# Amplifier.net
KiCad netlist of a schematic drawn in Altium Designer
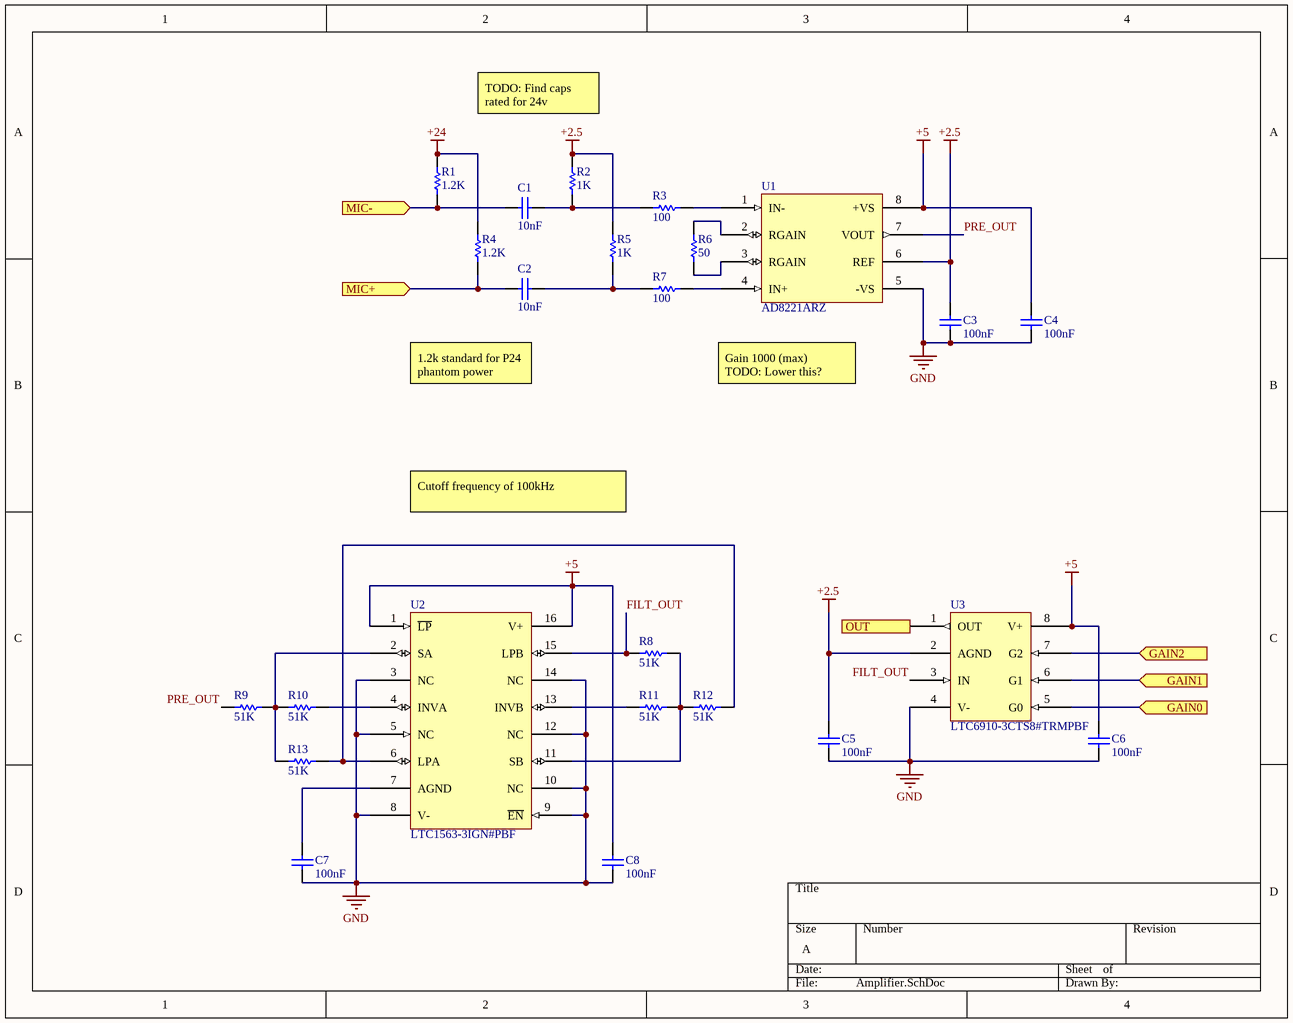
[diagram p0: Amplifier.SchDoc]

(export (version "E")
  (design (tool "Eeschema 10.0.6"))
  (components
    (comp (ref "C1")
      (value "10nF")
      (footprint "CAPC1608X10M")
      (description "GRM188 0603(1.6mm*0.8mm) ±5% and ±10% (15pF-2.2uF) SMD Capacitor")
      (fields (field (name "PUBLISHER") "Altium Limited"))
      (libsource (lib "Acoustics") (part "GRM188"))
    )
    (comp (ref "C2")
      (value "10nF")
      (footprint "CAPC1608X10M")
      (description "GRM188 0603(1.6mm*0.8mm) ±5% and ±10% (15pF-2.2uF) SMD Capacitor")
      (fields (field (name "PUBLISHER") "Altium Limited"))
      (libsource (lib "Acoustics") (part "GRM188"))
    )
    (comp (ref "C3")
      (value "100nF")
      (footprint "CAPC1608X10M")
      (description "GRM188 0603(1.6mm*0.8mm) ±5% and ±10% (15pF-2.2uF) SMD Capacitor")
      (fields (field (name "PUBLISHER") "Altium Limited"))
      (libsource (lib "Acoustics") (part "GRM188"))
    )
    (comp (ref "C4")
      (value "100nF")
      (footprint "CAPC1608X10M")
      (description "GRM188 0603(1.6mm*0.8mm) ±5% and ±10% (15pF-2.2uF) SMD Capacitor")
      (fields (field (name "PUBLISHER") "Altium Limited"))
      (libsource (lib "Acoustics") (part "GRM188"))
    )
    (comp (ref "C5")
      (value "100nF")
      (footprint "CAPC1608X10M")
      (description "GRM188 0603(1.6mm*0.8mm) ±5% and ±10% (15pF-2.2uF) SMD Capacitor")
      (fields (field (name "PUBLISHER") "Altium Limited"))
      (libsource (lib "Acoustics") (part "GRM188"))
    )
    (comp (ref "C6")
      (value "100nF")
      (footprint "CAPC1608X10M")
      (description "GRM188 0603(1.6mm*0.8mm) ±5% and ±10% (15pF-2.2uF) SMD Capacitor")
      (fields (field (name "PUBLISHER") "Altium Limited"))
      (libsource (lib "Acoustics") (part "GRM188"))
    )
    (comp (ref "C7")
      (value "100nF")
      (footprint "CAPC1608X10M")
      (description "GRM188 0603(1.6mm*0.8mm) ±5% and ±10% (15pF-2.2uF) SMD Capacitor")
      (fields (field (name "PUBLISHER") "Altium Limited"))
      (libsource (lib "Acoustics") (part "GRM188"))
    )
    (comp (ref "C8")
      (value "100nF")
      (footprint "CAPC1608X10M")
      (description "GRM188 0603(1.6mm*0.8mm) ±5% and ±10% (15pF-2.2uF) SMD Capacitor")
      (fields (field (name "PUBLISHER") "Altium Limited"))
      (libsource (lib "Acoustics") (part "GRM188"))
    )
    (comp (ref "R1")
      (value "1.2K")
      (footprint "RESC1608X06M")
      (description "RC0603 JR-07 0603 (1.6mm*0.8mm) ±1% 1% (0R-4.7MR) chip resistor")
      (fields (field (name "PUBLISHER") "Altium Limited"))
      (libsource (lib "Acoustics") (part "RC0603_JR07"))
    )
    (comp (ref "R2")
      (value "1K")
      (footprint "RESC1608X06M")
      (description "RC0603 JR-07 0603 (1.6mm*0.8mm) ±1% 1% (0R-4.7MR) chip resistor")
      (fields (field (name "PUBLISHER") "Altium Limited"))
      (libsource (lib "Acoustics") (part "RC0603_JR07"))
    )
    (comp (ref "R3")
      (value "100")
      (footprint "RESC1608X06M")
      (description "RC0603 JR-07 0603 (1.6mm*0.8mm) ±1% 1% (0R-4.7MR) chip resistor")
      (fields (field (name "PUBLISHER") "Altium Limited"))
      (libsource (lib "Acoustics") (part "RC0603_JR07"))
    )
    (comp (ref "R4")
      (value "1.2K")
      (footprint "RESC1608X06M")
      (description "RC0603 JR-07 0603 (1.6mm*0.8mm) ±1% 1% (0R-4.7MR) chip resistor")
      (fields (field (name "PUBLISHER") "Altium Limited"))
      (libsource (lib "Acoustics") (part "RC0603_JR07"))
    )
    (comp (ref "R5")
      (value "1K")
      (footprint "RESC1608X06M")
      (description "RC0603 JR-07 0603 (1.6mm*0.8mm) ±1% 1% (0R-4.7MR) chip resistor")
      (fields (field (name "PUBLISHER") "Altium Limited"))
      (libsource (lib "Acoustics") (part "RC0603_JR07"))
    )
    (comp (ref "R6")
      (value "50")
      (footprint "RESC1608X06M")
      (description "RC0603 JR-07 0603 (1.6mm*0.8mm) ±1% 1% (0R-4.7MR) chip resistor")
      (fields (field (name "PUBLISHER") "Altium Limited"))
      (libsource (lib "Acoustics") (part "RC0603_JR07"))
    )
    (comp (ref "R7")
      (value "100")
      (footprint "RESC1608X06M")
      (description "RC0603 JR-07 0603 (1.6mm*0.8mm) ±1% 1% (0R-4.7MR) chip resistor")
      (fields (field (name "PUBLISHER") "Altium Limited"))
      (libsource (lib "Acoustics") (part "RC0603_JR07"))
    )
    (comp (ref "R8")
      (value "51K")
      (footprint "RESC1608X06M")
      (description "RC0603 JR-07 0603 (1.6mm*0.8mm) ±1% 1% (0R-4.7MR) chip resistor")
      (fields (field (name "PUBLISHER") "Altium Limited"))
      (libsource (lib "Acoustics") (part "RC0603_JR07"))
    )
    (comp (ref "R9")
      (value "51K")
      (footprint "RESC1608X06M")
      (description "RC0603 JR-07 0603 (1.6mm*0.8mm) ±1% 1% (0R-4.7MR) chip resistor")
      (fields (field (name "PUBLISHER") "Altium Limited"))
      (libsource (lib "Acoustics") (part "RC0603_JR07"))
    )
    (comp (ref "R10")
      (value "51K")
      (footprint "RESC1608X06M")
      (description "RC0603 JR-07 0603 (1.6mm*0.8mm) ±1% 1% (0R-4.7MR) chip resistor")
      (fields (field (name "PUBLISHER") "Altium Limited"))
      (libsource (lib "Acoustics") (part "RC0603_JR07"))
    )
    (comp (ref "R11")
      (value "51K")
      (footprint "RESC1608X06M")
      (description "RC0603 JR-07 0603 (1.6mm*0.8mm) ±1% 1% (0R-4.7MR) chip resistor")
      (fields (field (name "PUBLISHER") "Altium Limited"))
      (libsource (lib "Acoustics") (part "RC0603_JR07"))
    )
    (comp (ref "R12")
      (value "51K")
      (footprint "RESC1608X06M")
      (description "RC0603 JR-07 0603 (1.6mm*0.8mm) ±1% 1% (0R-4.7MR) chip resistor")
      (fields (field (name "PUBLISHER") "Altium Limited"))
      (libsource (lib "Acoustics") (part "RC0603_JR07"))
    )
    (comp (ref "R13")
      (value "51K")
      (footprint "RESC1608X06M")
      (description "RC0603 JR-07 0603 (1.6mm*0.8mm) ±1% 1% (0R-4.7MR) chip resistor")
      (fields (field (name "PUBLISHER") "Altium Limited"))
      (libsource (lib "Acoustics") (part "RC0603_JR07"))
    )
    (comp (ref "U1")
      (value "AD8221ARZ")
      (footprint "SOIC127P600X150-8M")
      (description "IC INST AMP 1 CIRCUIT 8SOIC")
      (libsource (lib "Acoustics") (part "AD8221ARZ"))
    )
    (comp (ref "U2")
      (value "LTC1563-3IGN#PBF")
      (footprint "SOP64P600X175-16M")
      (description "IC FILTER 256KHZ LOWPASS BESSEL 16SSOP")
      (libsource (lib "Acoustics") (part "LTC1563-3IGN#PBF"))
    )
    (comp (ref "U3")
      (value "LTC6910-3CTS8#TRMPBF")
      (footprint "TSOP65P280X100-8M")
      (description "Programmable Gain Amplifier 1 Circuit Rail-to-Rail TSOT-23-8")
      (libsource (lib "Acoustics") (part "LTC6910-3CTS8#TRMPBF"))
    )
  )
  (nets
    (net (code "1") (name "+2.5") (class "Default")
      (node (ref "C3") (pin "2") (pinfunction "2_2") (pintype "passive"))
      (node (ref "C5") (pin "2") (pinfunction "2_2") (pintype "passive"))
      (node (ref "R2") (pin "2") (pinfunction "2_2") (pintype "passive"))
      (node (ref "R5") (pin "2") (pinfunction "2_2") (pintype "passive"))
      (node (ref "U1") (pin "6") (pinfunction "REF_6") (pintype "power_in"))
      (node (ref "U3") (pin "2") (pinfunction "AGND_2") (pintype "power_in"))
    )
    (net (code "2") (name "+5") (class "Default")
      (node (ref "C4") (pin "2") (pinfunction "2_2") (pintype "passive"))
      (node (ref "C6") (pin "2") (pinfunction "2_2") (pintype "passive"))
      (node (ref "C8") (pin "2") (pinfunction "2_2") (pintype "passive"))
      (node (ref "U1") (pin "8") (pinfunction "+VS_8") (pintype "power_in"))
      (node (ref "U2") (pin "1") (pinfunction "~{LP}_1") (pintype "input"))
      (node (ref "U2") (pin "16") (pinfunction "V+_16") (pintype "power_in"))
      (node (ref "U3") (pin "8") (pinfunction "V+_8") (pintype "power_in"))
    )
    (net (code "3") (name "+24") (class "Default")
      (node (ref "R1") (pin "2") (pinfunction "2_2") (pintype "passive"))
      (node (ref "R4") (pin "2") (pinfunction "2_2") (pintype "passive"))
    )
    (net (code "4") (name "/FILT_OUT") (class "Default")
      (node (ref "R8") (pin "2") (pinfunction "2_2") (pintype "passive"))
      (node (ref "U2") (pin "15") (pinfunction "LPB_15") (pintype "bidirectional"))
      (node (ref "U3") (pin "3") (pinfunction "IN_3") (pintype "input"))
    )
    (net (code "5") (name "/GAIN0") (class "Default")
      (node (ref "U3") (pin "5") (pinfunction "G0_5") (pintype "input"))
    )
    (net (code "6") (name "/GAIN1") (class "Default")
      (node (ref "U3") (pin "6") (pinfunction "G1_6") (pintype "input"))
    )
    (net (code "7") (name "/GAIN2") (class "Default")
      (node (ref "U3") (pin "7") (pinfunction "G2_7") (pintype "input"))
    )
    (net (code "8") (name "/MIC+") (class "Default")
      (node (ref "C2") (pin "1") (pinfunction "1_1") (pintype "passive"))
      (node (ref "R4") (pin "1") (pinfunction "1_1") (pintype "passive"))
    )
    (net (code "9") (name "/MIC-") (class "Default")
      (node (ref "C1") (pin "1") (pinfunction "1_1") (pintype "passive"))
      (node (ref "R1") (pin "1") (pinfunction "1_1") (pintype "passive"))
    )
    (net (code "10") (name "/OUT") (class "Default")
      (node (ref "U3") (pin "1") (pinfunction "OUT_1") (pintype "output"))
    )
    (net (code "11") (name "/PRE_OUT") (class "Default")
      (node (ref "R9") (pin "2") (pinfunction "2_2") (pintype "passive"))
      (node (ref "U1") (pin "7") (pinfunction "VOUT_7") (pintype "output"))
    )
    (net (code "12") (name "GND") (class "Default")
      (node (ref "C3") (pin "1") (pinfunction "1_1") (pintype "passive"))
      (node (ref "C4") (pin "1") (pinfunction "1_1") (pintype "passive"))
      (node (ref "C5") (pin "1") (pinfunction "1_1") (pintype "passive"))
      (node (ref "C6") (pin "1") (pinfunction "1_1") (pintype "passive"))
      (node (ref "C7") (pin "1") (pinfunction "1_1") (pintype "passive"))
      (node (ref "C8") (pin "1") (pinfunction "1_1") (pintype "passive"))
      (node (ref "U1") (pin "5") (pinfunction "-VS_5") (pintype "power_in"))
      (node (ref "U2") (pin "10") (pinfunction "NC_10") (pintype "power_in"))
      (node (ref "U2") (pin "12") (pinfunction "NC_12") (pintype "power_in"))
      (node (ref "U2") (pin "14") (pinfunction "NC_14") (pintype "power_in"))
      (node (ref "U2") (pin "3") (pinfunction "NC_3") (pintype "power_in"))
      (node (ref "U2") (pin "5") (pinfunction "NC_5") (pintype "input"))
      (node (ref "U2") (pin "8") (pinfunction "V-_8") (pintype "power_in"))
      (node (ref "U2") (pin "9") (pinfunction "~{EN}_9") (pintype "input"))
      (node (ref "U3") (pin "4") (pinfunction "V-_4") (pintype "power_in"))
    )
    (net (code "13") (name "Net-(C1-Pad2)") (class "Default")
      (node (ref "C1") (pin "2") (pinfunction "2_2") (pintype "passive"))
      (node (ref "R2") (pin "1") (pinfunction "1_1") (pintype "passive"))
      (node (ref "R3") (pin "2") (pinfunction "2_2") (pintype "passive"))
    )
    (net (code "14") (name "Net-(C2-Pad2)") (class "Default")
      (node (ref "C2") (pin "2") (pinfunction "2_2") (pintype "passive"))
      (node (ref "R5") (pin "1") (pinfunction "1_1") (pintype "passive"))
      (node (ref "R7") (pin "2") (pinfunction "2_2") (pintype "passive"))
    )
    (net (code "15") (name "Net-(R6-Pad1)") (class "Default")
      (node (ref "R6") (pin "1") (pinfunction "1_1") (pintype "passive"))
      (node (ref "U1") (pin "3") (pinfunction "RGAIN_3") (pintype "bidirectional"))
    )
    (net (code "16") (name "Net-(R6-Pad2)") (class "Default")
      (node (ref "R6") (pin "2") (pinfunction "2_2") (pintype "passive"))
      (node (ref "U1") (pin "2") (pinfunction "RGAIN_2") (pintype "bidirectional"))
    )
    (net (code "17") (name "Net-(U1-IN+)") (class "Default")
      (node (ref "R7") (pin "1") (pinfunction "1_1") (pintype "passive"))
      (node (ref "U1") (pin "4") (pinfunction "IN+_4") (pintype "input"))
    )
    (net (code "18") (name "Net-(U1-IN-)") (class "Default")
      (node (ref "R3") (pin "1") (pinfunction "1_1") (pintype "passive"))
      (node (ref "U1") (pin "1") (pinfunction "IN-_1") (pintype "input"))
    )
    (net (code "19") (name "Net-(U2-AGND)") (class "Default")
      (node (ref "C7") (pin "2") (pinfunction "2_2") (pintype "passive"))
      (node (ref "U2") (pin "7") (pinfunction "AGND_7") (pintype "power_in"))
    )
    (net (code "20") (name "Net-(U2-INVA)") (class "Default")
      (node (ref "R10") (pin "1") (pinfunction "1_1") (pintype "passive"))
      (node (ref "U2") (pin "4") (pinfunction "INVA_4") (pintype "bidirectional"))
    )
    (net (code "21") (name "Net-(U2-INVB)") (class "Default")
      (node (ref "R11") (pin "2") (pinfunction "2_2") (pintype "passive"))
      (node (ref "U2") (pin "13") (pinfunction "INVB_13") (pintype "bidirectional"))
    )
    (net (code "22") (name "Net-(U2-LPA)") (class "Default")
      (node (ref "R12") (pin "1") (pinfunction "1_1") (pintype "passive"))
      (node (ref "R13") (pin "2") (pinfunction "2_2") (pintype "passive"))
      (node (ref "U2") (pin "6") (pinfunction "LPA_6") (pintype "bidirectional"))
    )
    (net (code "23") (name "Net-(U2-SA)") (class "Default")
      (node (ref "R10") (pin "2") (pinfunction "2_2") (pintype "passive"))
      (node (ref "R13") (pin "1") (pinfunction "1_1") (pintype "passive"))
      (node (ref "R9") (pin "1") (pinfunction "1_1") (pintype "passive"))
      (node (ref "U2") (pin "2") (pinfunction "SA_2") (pintype "bidirectional"))
    )
    (net (code "24") (name "Net-(U2-SB)") (class "Default")
      (node (ref "R11") (pin "1") (pinfunction "1_1") (pintype "passive"))
      (node (ref "R12") (pin "2") (pinfunction "2_2") (pintype "passive"))
      (node (ref "R8") (pin "1") (pinfunction "1_1") (pintype "passive"))
      (node (ref "U2") (pin "11") (pinfunction "SB_11") (pintype "bidirectional"))
    )
  )
)
